# basic_circuit.net
KiCad netlist of a schematic drawn in EAGLE
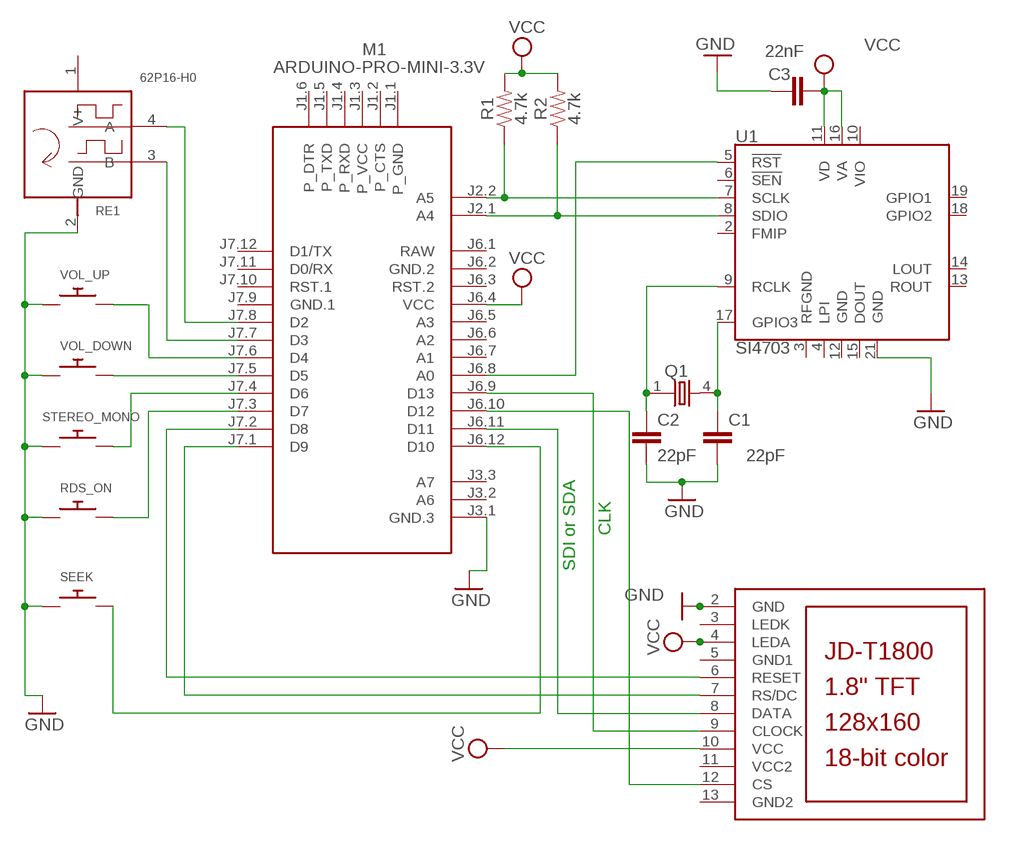
[diagram p0: schematic, sheet 1]

(export (version "E")
  (design (tool "Eeschema 10.0.6"))
  (components
    (comp (ref "C1")
      (value "22pF")
      (footprint "eagle-import:C2.5-3")
      (libsource (lib "eagle-import") (part "C2,5-3"))
    )
    (comp (ref "C2")
      (value "22pF")
      (footprint "eagle-import:C2.5-3")
      (libsource (lib "eagle-import") (part "C2,5-3"))
    )
    (comp (ref "C3")
      (value "22nF")
      (footprint "eagle-import:C2.5-3")
      (libsource (lib "eagle-import") (part "C2,5-3"))
    )
    (comp (ref "LCD1")
      (value "JD-T1800")
      (footprint "eagle-import:JD-T1800")
      (libsource (lib "eagle-import") (part "JD-T1800"))
    )
    (comp (ref "M1")
      (value "ARDUINO-PRO-MINI-3.3V")
      (footprint "eagle-import:ARDUINO-PRO-MINI")
      (libsource (lib "eagle-import") (part "ARDUINO-PRO-MINI-3.3V"))
    )
    (comp (ref "Q1")
      (value "86SMX")
      (footprint "eagle-import:86SMX")
      (fields (field (name "MF") "C-MAC  FREQUENCY PRODUCTS LTD") (field (name "MPN") "XTAL003321- 86SMX"))
      (libsource (lib "eagle-import") (part "86SMX"))
    )
    (comp (ref "R1")
      (value "4.7k")
      (footprint "eagle-import:0603")
      (libsource (lib "eagle-import") (part "4.7KOHM-0603-1/10W-1%"))
    )
    (comp (ref "R2")
      (value "4.7k")
      (footprint "eagle-import:0603")
      (libsource (lib "eagle-import") (part "4.7KOHM-0603-1/10W-1%"))
    )
    (comp (ref "RDS_ON")
      (value "SWITCH_PUSHBUTTONC&K_KSS")
      (footprint "eagle-import:BTN_CK_KSS")
      (libsource (lib "eagle-import") (part "SWITCH_PUSHBUTTONC&K_KSS"))
    )
    (comp (ref "RE1")
      (value "62P16-H0")
      (footprint "eagle-import:62P")
      (libsource (lib "eagle-import") (part "62P016-H"))
    )
    (comp (ref "SEEK")
      (value "SWITCH_PUSHBUTTONC&K_KSS")
      (footprint "eagle-import:BTN_CK_KSS")
      (libsource (lib "eagle-import") (part "SWITCH_PUSHBUTTONC&K_KSS"))
    )
    (comp (ref "STEREO_MONO")
      (value "SWITCH_PUSHBUTTONC&K_KSS")
      (footprint "eagle-import:BTN_CK_KSS")
      (libsource (lib "eagle-import") (part "SWITCH_PUSHBUTTONC&K_KSS"))
    )
    (comp (ref "U1")
      (value "SI4703")
      (footprint "eagle-import:QFN-20-3X3MM")
      (fields (field (name "MF") "SparkFun Electronics"))
      (libsource (lib "eagle-import") (part "SI4703"))
    )
    (comp (ref "VOL_DOWN")
      (value "SWITCH_PUSHBUTTONC&K_KSS")
      (footprint "eagle-import:BTN_CK_KSS")
      (libsource (lib "eagle-import") (part "SWITCH_PUSHBUTTONC&K_KSS"))
    )
    (comp (ref "VOL_UP")
      (value "SWITCH_PUSHBUTTONC&K_KSS")
      (footprint "eagle-import:BTN_CK_KSS")
      (libsource (lib "eagle-import") (part "SWITCH_PUSHBUTTONC&K_KSS"))
    )
  )
  (nets
    (net (code "1") (name "/GND.1") (class "Default")
      (node (ref "M1") (pin "J7.9") (pinfunction "GND.1_J7.9") (pintype "power_in"))
    )
    (net (code "2") (name "/GND.2") (class "Default")
      (node (ref "M1") (pin "J6.2") (pinfunction "GND.2_J6.2") (pintype "power_in"))
    )
    (net (code "3") (name "/GND1") (class "Default")
      (node (ref "LCD1") (pin "5") (pinfunction "GND1_5") (pintype "power_in"))
    )
    (net (code "4") (name "/GND2") (class "Default")
      (node (ref "LCD1") (pin "13") (pinfunction "GND2_13") (pintype "power_in"))
    )
    (net (code "5") (name "/RAW") (class "Default")
      (node (ref "M1") (pin "J6.1") (pinfunction "RAW_J6.1") (pintype "power_in"))
    )
    (net (code "6") (name "/V+") (class "Default")
      (node (ref "RE1") (pin "1") (pinfunction "V+_1") (pintype "power_in"))
    )
    (net (code "7") (name "/VCC2") (class "Default")
      (node (ref "LCD1") (pin "11") (pinfunction "VCC2_11") (pintype "power_in"))
    )
    (net (code "8") (name "GND") (class "Default")
      (node (ref "C1") (pin "2") (pinfunction "2_2") (pintype "passive"))
      (node (ref "C2") (pin "2") (pinfunction "2_2") (pintype "passive"))
      (node (ref "C3") (pin "1") (pinfunction "1_1") (pintype "passive"))
      (node (ref "LCD1") (pin "2") (pinfunction "GND_2") (pintype "power_in"))
      (node (ref "M1") (pin "J3.1") (pinfunction "GND.3_J3.1") (pintype "bidirectional"))
      (node (ref "RDS_ON") (pin "P$1") (pinfunction "P$1_P$1") (pintype "passive"))
      (node (ref "RE1") (pin "2") (pinfunction "GND_2") (pintype "power_in"))
      (node (ref "SEEK") (pin "P$1") (pinfunction "P$1_P$1") (pintype "passive"))
      (node (ref "STEREO_MONO") (pin "P$1") (pinfunction "P$1_P$1") (pintype "passive"))
      (node (ref "U1") (pin "21") (pinfunction "GND_21") (pintype "bidirectional"))
      (node (ref "VOL_DOWN") (pin "P$1") (pinfunction "P$1_P$1") (pintype "passive"))
      (node (ref "VOL_UP") (pin "P$1") (pinfunction "P$1_P$1") (pintype "passive"))
    )
    (net (code "9") (name "Net-(LCD1-CLOCK)") (class "Default")
      (node (ref "LCD1") (pin "9") (pinfunction "CLOCK_9") (pintype "input"))
      (node (ref "M1") (pin "J6.9") (pinfunction "D13_J6.9") (pintype "bidirectional"))
    )
    (net (code "10") (name "Net-(LCD1-CS)") (class "Default")
      (node (ref "LCD1") (pin "12") (pinfunction "CS_12") (pintype "input"))
      (node (ref "M1") (pin "J6.10") (pinfunction "D12_J6.10") (pintype "bidirectional"))
    )
    (net (code "11") (name "Net-(LCD1-DATA)") (class "Default")
      (node (ref "LCD1") (pin "8") (pinfunction "DATA_8") (pintype "bidirectional"))
      (node (ref "M1") (pin "J6.11") (pinfunction "D11_J6.11") (pintype "bidirectional"))
    )
    (net (code "12") (name "Net-(LCD1-RESET)") (class "Default")
      (node (ref "LCD1") (pin "6") (pinfunction "RESET_6") (pintype "input"))
      (node (ref "M1") (pin "J7.2") (pinfunction "D8_J7.2") (pintype "bidirectional"))
    )
    (net (code "13") (name "Net-(LCD1-RS{slash}DC)") (class "Default")
      (node (ref "LCD1") (pin "7") (pinfunction "RS/DC_7") (pintype "input"))
      (node (ref "M1") (pin "J7.1") (pinfunction "D9_J7.1") (pintype "bidirectional"))
    )
    (net (code "14") (name "Net-(M1-A0)") (class "Default")
      (node (ref "M1") (pin "J6.8") (pinfunction "A0_J6.8") (pintype "bidirectional"))
      (node (ref "U1") (pin "5") (pinfunction "~{RST}_5") (pintype "bidirectional"))
    )
    (net (code "15") (name "Net-(M1-A4)") (class "Default")
      (node (ref "M1") (pin "J2.1") (pinfunction "A4_J2.1") (pintype "bidirectional"))
      (node (ref "R2") (pin "1") (pinfunction "1_1") (pintype "passive"))
      (node (ref "U1") (pin "8") (pinfunction "SDIO_8") (pintype "bidirectional"))
    )
    (net (code "16") (name "Net-(M1-A5)") (class "Default")
      (node (ref "M1") (pin "J2.2") (pinfunction "A5_J2.2") (pintype "bidirectional"))
      (node (ref "R1") (pin "1") (pinfunction "1_1") (pintype "passive"))
      (node (ref "U1") (pin "7") (pinfunction "SCLK_7") (pintype "bidirectional"))
    )
    (net (code "17") (name "Net-(M1-D2)") (class "Default")
      (node (ref "M1") (pin "J7.8") (pinfunction "D2_J7.8") (pintype "bidirectional"))
      (node (ref "RE1") (pin "4") (pinfunction "A_4") (pintype "bidirectional"))
    )
    (net (code "18") (name "Net-(M1-D3)") (class "Default")
      (node (ref "M1") (pin "J7.7") (pinfunction "D3_J7.7") (pintype "bidirectional"))
      (node (ref "RE1") (pin "3") (pinfunction "B_3") (pintype "bidirectional"))
    )
    (net (code "19") (name "Net-(M1-D4)") (class "Default")
      (node (ref "M1") (pin "J7.6") (pinfunction "D4_J7.6") (pintype "bidirectional"))
      (node (ref "VOL_UP") (pin "P$2") (pinfunction "P$2_P$2") (pintype "passive"))
    )
    (net (code "20") (name "Net-(M1-D5)") (class "Default")
      (node (ref "M1") (pin "J7.5") (pinfunction "D5_J7.5") (pintype "bidirectional"))
      (node (ref "VOL_DOWN") (pin "P$2") (pinfunction "P$2_P$2") (pintype "passive"))
    )
    (net (code "21") (name "Net-(M1-D6)") (class "Default")
      (node (ref "M1") (pin "J7.4") (pinfunction "D6_J7.4") (pintype "bidirectional"))
      (node (ref "STEREO_MONO") (pin "P$2") (pinfunction "P$2_P$2") (pintype "passive"))
    )
    (net (code "22") (name "Net-(M1-D7)") (class "Default")
      (node (ref "M1") (pin "J7.3") (pinfunction "D7_J7.3") (pintype "bidirectional"))
      (node (ref "RDS_ON") (pin "P$2") (pinfunction "P$2_P$2") (pintype "passive"))
    )
    (net (code "23") (name "Net-(M1-D10)") (class "Default")
      (node (ref "M1") (pin "J6.12") (pinfunction "D10_J6.12") (pintype "bidirectional"))
      (node (ref "SEEK") (pin "P$2") (pinfunction "P$2_P$2") (pintype "passive"))
    )
    (net (code "24") (name "Net-(Q1-2)") (class "Default")
      (node (ref "C1") (pin "1") (pinfunction "1_1") (pintype "passive"))
      (node (ref "Q1") (pin "4") (pinfunction "2_4") (pintype "passive"))
      (node (ref "U1") (pin "17") (pinfunction "GPIO3_17") (pintype "bidirectional"))
    )
    (net (code "25") (name "Net-(U1-RCLK)") (class "Default")
      (node (ref "C2") (pin "1") (pinfunction "1_1") (pintype "passive"))
      (node (ref "Q1") (pin "1") (pinfunction "1_1") (pintype "passive"))
      (node (ref "U1") (pin "9") (pinfunction "RCLK_9") (pintype "bidirectional"))
    )
    (net (code "26") (name "VCC") (class "Default")
      (node (ref "C3") (pin "2") (pinfunction "2_2") (pintype "passive"))
      (node (ref "LCD1") (pin "10") (pinfunction "VCC_10") (pintype "power_in"))
      (node (ref "LCD1") (pin "4") (pinfunction "LEDA_4") (pintype "input"))
      (node (ref "M1") (pin "J6.4") (pinfunction "VCC_J6.4") (pintype "power_in"))
      (node (ref "R1") (pin "2") (pinfunction "2_2") (pintype "passive"))
      (node (ref "R2") (pin "2") (pinfunction "2_2") (pintype "passive"))
      (node (ref "U1") (pin "11") (pinfunction "VD_11") (pintype "bidirectional"))
      (node (ref "U1") (pin "16") (pinfunction "VA_16") (pintype "bidirectional"))
    )
    (net (code "27") (name "unconnected-(LCD1-LEDK-Pad3)") (class "Default")
      (node (ref "LCD1") (pin "3") (pinfunction "LEDK_3") (pintype "input"))
    )
    (net (code "28") (name "unconnected-(M1-A1-PadJ6.7)") (class "Default")
      (node (ref "M1") (pin "J6.7") (pinfunction "A1_J6.7") (pintype "bidirectional"))
    )
    (net (code "29") (name "unconnected-(M1-A2-PadJ6.6)") (class "Default")
      (node (ref "M1") (pin "J6.6") (pinfunction "A2_J6.6") (pintype "bidirectional"))
    )
    (net (code "30") (name "unconnected-(M1-A3-PadJ6.5)") (class "Default")
      (node (ref "M1") (pin "J6.5") (pinfunction "A3_J6.5") (pintype "bidirectional"))
    )
    (net (code "31") (name "unconnected-(M1-A6-PadJ3.2)") (class "Default")
      (node (ref "M1") (pin "J3.2") (pinfunction "A6_J3.2") (pintype "bidirectional"))
    )
    (net (code "32") (name "unconnected-(M1-A7-PadJ3.3)") (class "Default")
      (node (ref "M1") (pin "J3.3") (pinfunction "A7_J3.3") (pintype "bidirectional"))
    )
    (net (code "33") (name "unconnected-(M1-D0{slash}RX-PadJ7.11)") (class "Default")
      (node (ref "M1") (pin "J7.11") (pinfunction "D0/RX_J7.11") (pintype "bidirectional"))
    )
    (net (code "34") (name "unconnected-(M1-D1{slash}TX-PadJ7.12)") (class "Default")
      (node (ref "M1") (pin "J7.12") (pinfunction "D1/TX_J7.12") (pintype "bidirectional"))
    )
    (net (code "35") (name "unconnected-(M1-P_CTS-PadJ1.2)") (class "Default")
      (node (ref "M1") (pin "J1.2") (pinfunction "P_CTS_J1.2") (pintype "bidirectional"))
    )
    (net (code "36") (name "unconnected-(M1-P_DTR-PadJ1.6)") (class "Default")
      (node (ref "M1") (pin "J1.6") (pinfunction "P_DTR_J1.6") (pintype "bidirectional"))
    )
    (net (code "37") (name "unconnected-(M1-P_GND-PadJ1.1)") (class "Default")
      (node (ref "M1") (pin "J1.1") (pinfunction "P_GND_J1.1") (pintype "bidirectional"))
    )
    (net (code "38") (name "unconnected-(M1-P_RXD-PadJ1.4)") (class "Default")
      (node (ref "M1") (pin "J1.4") (pinfunction "P_RXD_J1.4") (pintype "bidirectional"))
    )
    (net (code "39") (name "unconnected-(M1-P_TXD-PadJ1.5)") (class "Default")
      (node (ref "M1") (pin "J1.5") (pinfunction "P_TXD_J1.5") (pintype "bidirectional"))
    )
    (net (code "40") (name "unconnected-(M1-P_VCC-PadJ1.3)") (class "Default")
      (node (ref "M1") (pin "J1.3") (pinfunction "P_VCC_J1.3") (pintype "bidirectional"))
    )
    (net (code "41") (name "unconnected-(M1-RST.1-PadJ7.10)") (class "Default")
      (node (ref "M1") (pin "J7.10") (pinfunction "RST.1_J7.10") (pintype "bidirectional"))
    )
    (net (code "42") (name "unconnected-(M1-RST.2-PadJ6.3)") (class "Default")
      (node (ref "M1") (pin "J6.3") (pinfunction "RST.2_J6.3") (pintype "bidirectional"))
    )
    (net (code "43") (name "unconnected-(U1-DOUT-Pad15)") (class "Default")
      (node (ref "U1") (pin "15") (pinfunction "DOUT_15") (pintype "bidirectional"))
    )
    (net (code "44") (name "unconnected-(U1-FMIP-Pad2)") (class "Default")
      (node (ref "U1") (pin "2") (pinfunction "FMIP_2") (pintype "bidirectional"))
    )
    (net (code "45") (name "unconnected-(U1-GND-Pad12)") (class "Default")
      (node (ref "U1") (pin "12") (pinfunction "GND_12") (pintype "bidirectional"))
    )
    (net (code "46") (name "unconnected-(U1-GPIO1-Pad19)") (class "Default")
      (node (ref "U1") (pin "19") (pinfunction "GPIO1_19") (pintype "bidirectional"))
    )
    (net (code "47") (name "unconnected-(U1-GPIO2-Pad18)") (class "Default")
      (node (ref "U1") (pin "18") (pinfunction "GPIO2_18") (pintype "bidirectional"))
    )
    (net (code "48") (name "unconnected-(U1-LOUT-Pad14)") (class "Default")
      (node (ref "U1") (pin "14") (pinfunction "LOUT_14") (pintype "bidirectional"))
    )
    (net (code "49") (name "unconnected-(U1-LPI-Pad4)") (class "Default")
      (node (ref "U1") (pin "4") (pinfunction "LPI_4") (pintype "bidirectional"))
    )
    (net (code "50") (name "unconnected-(U1-RFGND-Pad3)") (class "Default")
      (node (ref "U1") (pin "3") (pinfunction "RFGND_3") (pintype "bidirectional"))
    )
    (net (code "51") (name "unconnected-(U1-ROUT-Pad13)") (class "Default")
      (node (ref "U1") (pin "13") (pinfunction "ROUT_13") (pintype "bidirectional"))
    )
    (net (code "52") (name "unconnected-(U1-VIO-Pad10)") (class "Default")
      (node (ref "U1") (pin "10") (pinfunction "VIO_10") (pintype "bidirectional"))
    )
    (net (code "53") (name "unconnected-(U1-~{SEN}-Pad6)") (class "Default")
      (node (ref "U1") (pin "6") (pinfunction "~{SEN}_6") (pintype "bidirectional"))
    )
  )
)
